# BlueSMiRF-ChipAnt.net
KiCad netlist of a schematic drawn in EAGLE
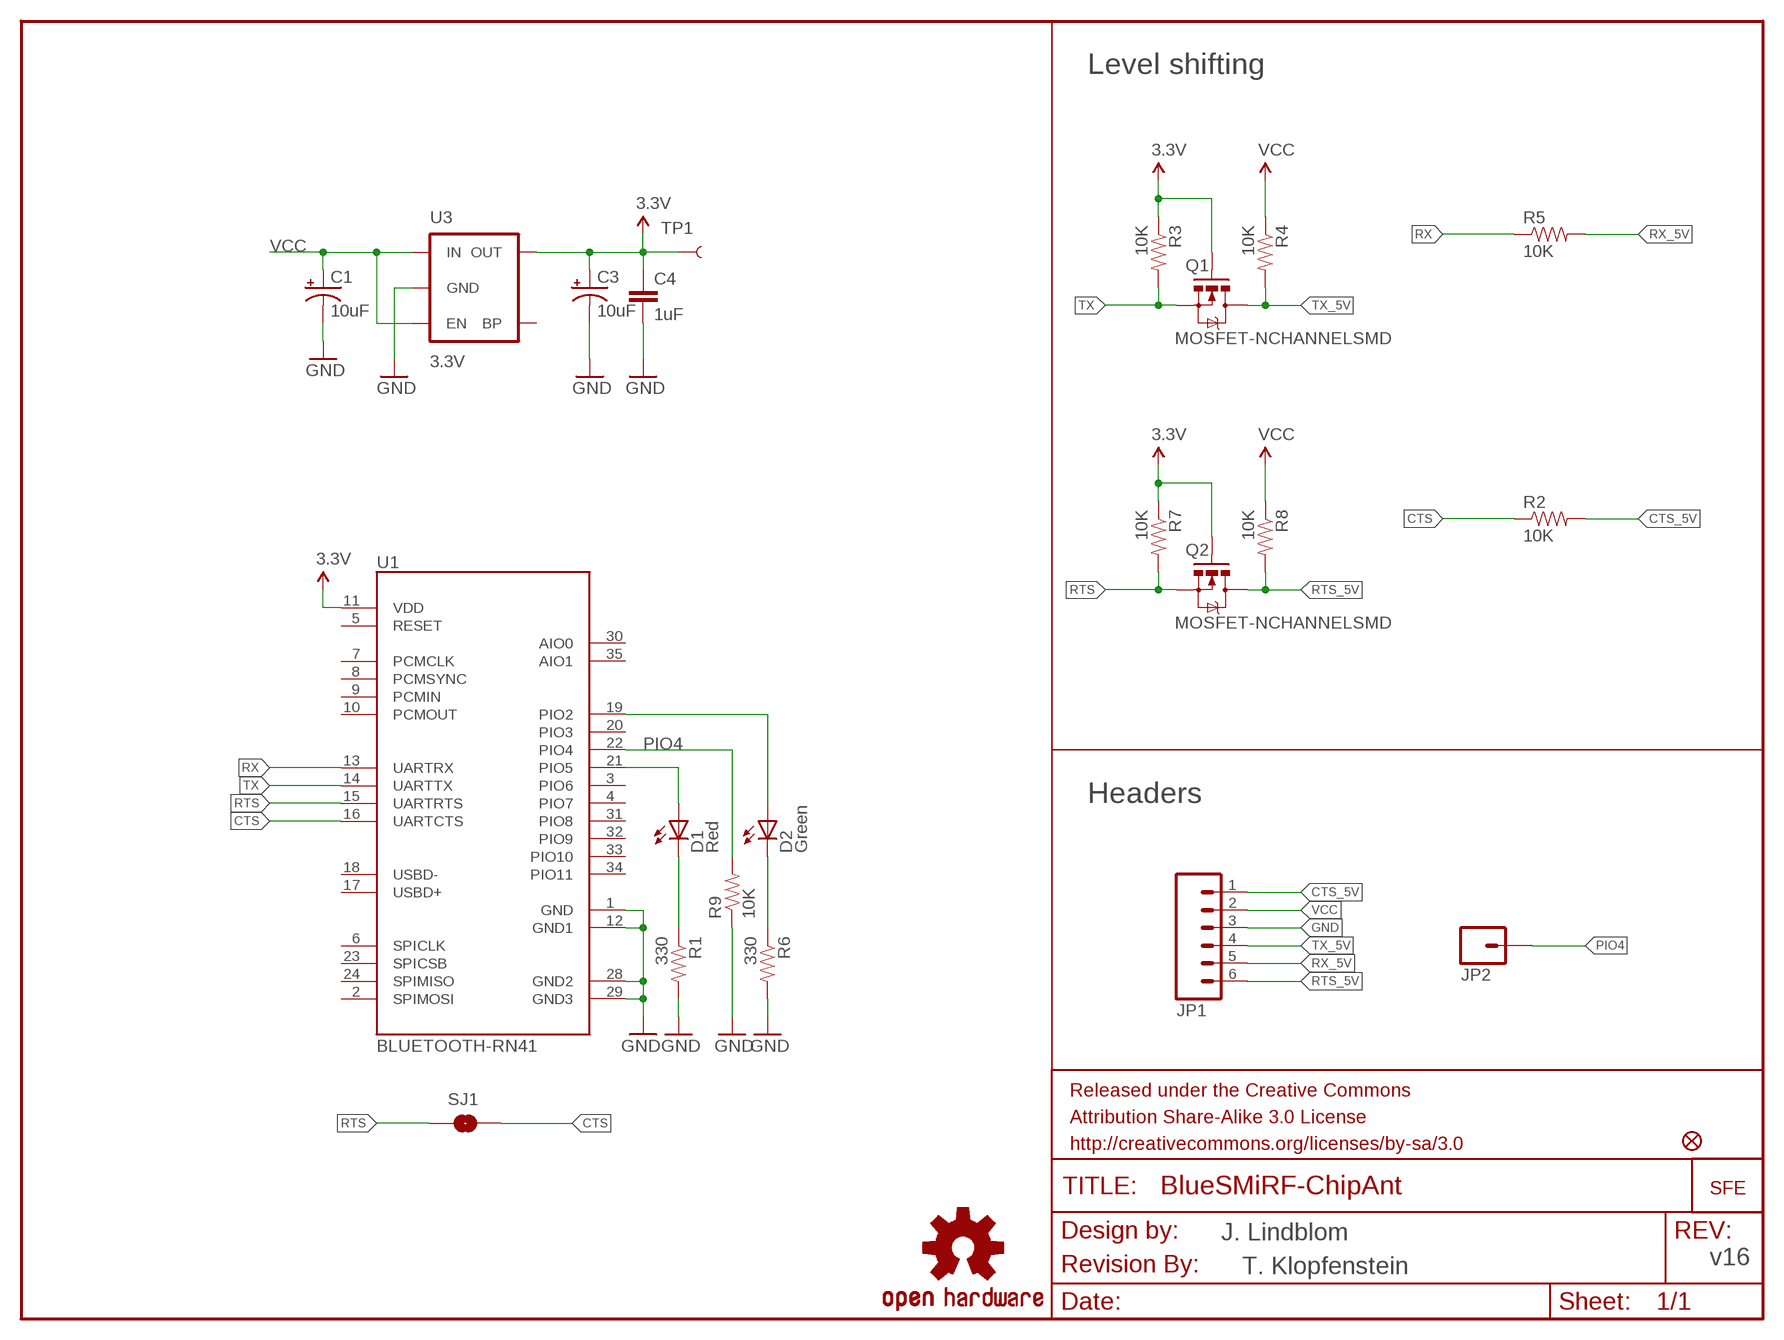
[diagram p0: schematic, sheet 1]

(export (version "E")
  (design (tool "Eeschema 10.0.6"))
  (components
    (comp (ref "C1")
      (value "10uF")
      (footprint "eagle-import:EIA3216")
      (libsource (lib "eagle-import") (part "CAP_POL1206"))
    )
    (comp (ref "C3")
      (value "10uF")
      (footprint "eagle-import:EIA3216")
      (libsource (lib "eagle-import") (part "CAP_POL1206"))
    )
    (comp (ref "C4")
      (value "1uF")
      (footprint "eagle-import:0603-CAP")
      (libsource (lib "eagle-import") (part "CAP0603-CAP"))
    )
    (comp (ref "D1")
      (value "Red")
      (footprint "eagle-import:LED-0603")
      (libsource (lib "eagle-import") (part "LED0603"))
    )
    (comp (ref "D2")
      (value "Green")
      (footprint "eagle-import:LED-0603")
      (libsource (lib "eagle-import") (part "LED0603"))
    )
    (comp (ref "FRAME1")
      (value "FRAME-LETTER")
      (footprint "eagle-import:CREATIVE_COMMONS")
      (libsource (lib "eagle-import") (part "FRAME-LETTER"))
    )
    (comp (ref "JP1")
      (value "M06SIP")
      (footprint "eagle-import:1X06")
      (libsource (lib "eagle-import") (part "M06SIP"))
    )
    (comp (ref "JP2")
      (value "M01SMDNS")
      (footprint "eagle-import:1X01NS")
      (libsource (lib "eagle-import") (part "M01SMDNS"))
    )
    (comp (ref "JP4")
      (value "FIDUCIAL1X2")
      (footprint "eagle-import:FIDUCIAL-1X2")
      (libsource (lib "eagle-import") (part "FIDUCIAL1X2"))
    )
    (comp (ref "LOGO1")
      (value "OSHW-LOGOS")
      (footprint "eagle-import:OSHW-LOGO-S")
      (libsource (lib "eagle-import") (part "OSHW-LOGOS"))
    )
    (comp (ref "Q1")
      (value "MOSFET-NCHANNELSMD")
      (footprint "eagle-import:SOT23-3")
      (libsource (lib "eagle-import") (part "MOSFET-NCHANNELSMD"))
    )
    (comp (ref "Q2")
      (value "MOSFET-NCHANNELSMD")
      (footprint "eagle-import:SOT23-3")
      (libsource (lib "eagle-import") (part "MOSFET-NCHANNELSMD"))
    )
    (comp (ref "R1")
      (value "330")
      (footprint "eagle-import:0603-RES")
      (libsource (lib "eagle-import") (part "RESISTOR0603-RES"))
    )
    (comp (ref "R2")
      (value "10K")
      (footprint "eagle-import:0603-RES")
      (libsource (lib "eagle-import") (part "RESISTOR0603-RES"))
    )
    (comp (ref "R3")
      (value "10K")
      (footprint "eagle-import:0603-RES")
      (libsource (lib "eagle-import") (part "RESISTOR0603-RES"))
    )
    (comp (ref "R4")
      (value "10K")
      (footprint "eagle-import:0603-RES")
      (libsource (lib "eagle-import") (part "RESISTOR0603-RES"))
    )
    (comp (ref "R5")
      (value "10K")
      (footprint "eagle-import:0603-RES")
      (libsource (lib "eagle-import") (part "RESISTOR0603-RES"))
    )
    (comp (ref "R6")
      (value "330")
      (footprint "eagle-import:0603-RES")
      (libsource (lib "eagle-import") (part "RESISTOR0603-RES"))
    )
    (comp (ref "R7")
      (value "10K")
      (footprint "eagle-import:0603-RES")
      (libsource (lib "eagle-import") (part "RESISTOR0603-RES"))
    )
    (comp (ref "R8")
      (value "10K")
      (footprint "eagle-import:0603-RES")
      (libsource (lib "eagle-import") (part "RESISTOR0603-RES"))
    )
    (comp (ref "R9")
      (value "10K")
      (footprint "eagle-import:0603-RES")
      (libsource (lib "eagle-import") (part "RESISTOR0603-RES"))
    )
    (comp (ref "SJ1")
      (value "SOLDERJUMPERNO")
      (footprint "eagle-import:SJ_2S-NO")
      (libsource (lib "eagle-import") (part "SOLDERJUMPERNO"))
    )
    (comp (ref "TP1")
      (value "TEST-POINT3X5")
      (footprint "eagle-import:PAD.03X.05")
      (libsource (lib "eagle-import") (part "TEST-POINT3X5"))
    )
    (comp (ref "U$1")
      (value "LOGO-SFENEW")
      (footprint "eagle-import:SFE-NEW-WEBLOGO")
      (libsource (lib "eagle-import") (part "LOGO-SFENEW"))
    )
    (comp (ref "U$2")
      (value "REVISION")
      (footprint "eagle-import:REVISION")
      (libsource (lib "eagle-import") (part "REVISION"))
    )
    (comp (ref "U1")
      (value "BLUETOOTH-RN41")
      (footprint "eagle-import:RN41")
      (libsource (lib "eagle-import") (part "BLUETOOTH-RN41{dblquote}"))
    )
    (comp (ref "U3")
      (value "3.3V")
      (footprint "eagle-import:SOT23-5")
      (libsource (lib "eagle-import") (part "V_REG_LDOSMD"))
    )
  )
  (nets
    (net (code "1") (name "3.3V") (class "Default")
      (node (ref "C3") (pin "A") (pinfunction "+_A") (pintype "passive"))
      (node (ref "C4") (pin "1") (pinfunction "1_1") (pintype "passive"))
      (node (ref "Q1") (pin "1") (pinfunction "G_1") (pintype "passive"))
      (node (ref "Q2") (pin "1") (pinfunction "G_1") (pintype "passive"))
      (node (ref "R3") (pin "1") (pinfunction "1_1") (pintype "passive"))
      (node (ref "R7") (pin "1") (pinfunction "1_1") (pintype "passive"))
      (node (ref "TP1") (pin "P$1") (pinfunction "1_P$1") (pintype "bidirectional"))
      (node (ref "U1") (pin "11") (pinfunction "VDD_11") (pintype "bidirectional"))
      (node (ref "U3") (pin "5") (pinfunction "OUT_5") (pintype "passive"))
    )
    (net (code "2") (name "CTS") (class "Default")
      (node (ref "R2") (pin "1") (pinfunction "1_1") (pintype "passive"))
      (node (ref "SJ1") (pin "2") (pinfunction "2_2") (pintype "passive"))
      (node (ref "U1") (pin "16") (pinfunction "UARTCTS_16") (pintype "bidirectional"))
    )
    (net (code "3") (name "CTS_5V") (class "Default")
      (node (ref "JP1") (pin "1") (pinfunction "1_1") (pintype "passive"))
      (node (ref "R2") (pin "2") (pinfunction "2_2") (pintype "passive"))
    )
    (net (code "4") (name "GND") (class "Default")
      (node (ref "C1") (pin "C") (pinfunction "-_C") (pintype "passive"))
      (node (ref "C3") (pin "C") (pinfunction "-_C") (pintype "passive"))
      (node (ref "C4") (pin "2") (pinfunction "2_2") (pintype "passive"))
      (node (ref "JP1") (pin "3") (pinfunction "3_3") (pintype "passive"))
      (node (ref "R1") (pin "2") (pinfunction "2_2") (pintype "passive"))
      (node (ref "R6") (pin "2") (pinfunction "2_2") (pintype "passive"))
      (node (ref "R9") (pin "1") (pinfunction "1_1") (pintype "passive"))
      (node (ref "U1") (pin "1") (pinfunction "GND_1") (pintype "bidirectional"))
      (node (ref "U1") (pin "12") (pinfunction "GND1_12") (pintype "bidirectional"))
      (node (ref "U1") (pin "28") (pinfunction "GND2_28") (pintype "bidirectional"))
      (node (ref "U1") (pin "29") (pinfunction "GND3_29") (pintype "bidirectional"))
      (node (ref "U3") (pin "2") (pinfunction "GND_2") (pintype "input"))
    )
    (net (code "5") (name "Net-(D1-PadC)") (class "Default")
      (node (ref "D1") (pin "C") (pinfunction "C_C") (pintype "passive"))
      (node (ref "R1") (pin "1") (pinfunction "1_1") (pintype "passive"))
    )
    (net (code "6") (name "Net-(D2-PadC)") (class "Default")
      (node (ref "D2") (pin "C") (pinfunction "C_C") (pintype "passive"))
      (node (ref "R6") (pin "1") (pinfunction "1_1") (pintype "passive"))
    )
    (net (code "7") (name "Net-(U1-PIO2)") (class "Default")
      (node (ref "D2") (pin "A") (pinfunction "A_A") (pintype "passive"))
      (node (ref "U1") (pin "19") (pinfunction "PIO2_19") (pintype "bidirectional"))
    )
    (net (code "8") (name "Net-(U1-PIO5)") (class "Default")
      (node (ref "D1") (pin "A") (pinfunction "A_A") (pintype "passive"))
      (node (ref "U1") (pin "21") (pinfunction "PIO5_21") (pintype "bidirectional"))
    )
    (net (code "9") (name "PIO4") (class "Default")
      (node (ref "JP2") (pin "1") (pinfunction "1_1") (pintype "passive"))
      (node (ref "R9") (pin "2") (pinfunction "2_2") (pintype "passive"))
      (node (ref "U1") (pin "22") (pinfunction "PIO4_22") (pintype "bidirectional"))
    )
    (net (code "10") (name "RTS") (class "Default")
      (node (ref "Q2") (pin "2") (pinfunction "S_2") (pintype "passive"))
      (node (ref "R7") (pin "2") (pinfunction "2_2") (pintype "passive"))
      (node (ref "SJ1") (pin "1") (pinfunction "1_1") (pintype "passive"))
      (node (ref "U1") (pin "15") (pinfunction "UARTRTS_15") (pintype "bidirectional"))
    )
    (net (code "11") (name "RTS_5V") (class "Default")
      (node (ref "JP1") (pin "6") (pinfunction "6_6") (pintype "passive"))
      (node (ref "Q2") (pin "3") (pinfunction "D_3") (pintype "passive"))
      (node (ref "R8") (pin "2") (pinfunction "2_2") (pintype "passive"))
    )
    (net (code "12") (name "RX") (class "Default")
      (node (ref "R5") (pin "1") (pinfunction "1_1") (pintype "passive"))
      (node (ref "U1") (pin "13") (pinfunction "UARTRX_13") (pintype "bidirectional"))
    )
    (net (code "13") (name "RX_5V") (class "Default")
      (node (ref "JP1") (pin "5") (pinfunction "5_5") (pintype "passive"))
      (node (ref "R5") (pin "2") (pinfunction "2_2") (pintype "passive"))
    )
    (net (code "14") (name "TX") (class "Default")
      (node (ref "Q1") (pin "2") (pinfunction "S_2") (pintype "passive"))
      (node (ref "R3") (pin "2") (pinfunction "2_2") (pintype "passive"))
      (node (ref "U1") (pin "14") (pinfunction "UARTTX_14") (pintype "bidirectional"))
    )
    (net (code "15") (name "TX_5V") (class "Default")
      (node (ref "JP1") (pin "4") (pinfunction "4_4") (pintype "passive"))
      (node (ref "Q1") (pin "3") (pinfunction "D_3") (pintype "passive"))
      (node (ref "R4") (pin "2") (pinfunction "2_2") (pintype "passive"))
    )
    (net (code "16") (name "VCC") (class "Default")
      (node (ref "C1") (pin "A") (pinfunction "+_A") (pintype "passive"))
      (node (ref "JP1") (pin "2") (pinfunction "2_2") (pintype "passive"))
      (node (ref "R4") (pin "1") (pinfunction "1_1") (pintype "passive"))
      (node (ref "R8") (pin "1") (pinfunction "1_1") (pintype "passive"))
      (node (ref "U3") (pin "1") (pinfunction "IN_1") (pintype "input"))
      (node (ref "U3") (pin "3") (pinfunction "EN_3") (pintype "input"))
    )
    (net (code "17") (name "unconnected-(U1-AIO0-Pad30)") (class "Default")
      (node (ref "U1") (pin "30") (pinfunction "AIO0_30") (pintype "bidirectional"))
    )
    (net (code "18") (name "unconnected-(U1-AIO1-Pad35)") (class "Default")
      (node (ref "U1") (pin "35") (pinfunction "AIO1_35") (pintype "bidirectional"))
    )
    (net (code "19") (name "unconnected-(U1-PCMCLK-Pad7)") (class "Default")
      (node (ref "U1") (pin "7") (pinfunction "PCMCLK_7") (pintype "bidirectional"))
    )
    (net (code "20") (name "unconnected-(U1-PCMIN-Pad9)") (class "Default")
      (node (ref "U1") (pin "9") (pinfunction "PCMIN_9") (pintype "bidirectional"))
    )
    (net (code "21") (name "unconnected-(U1-PCMOUT-Pad10)") (class "Default")
      (node (ref "U1") (pin "10") (pinfunction "PCMOUT_10") (pintype "bidirectional"))
    )
    (net (code "22") (name "unconnected-(U1-PCMSYNC-Pad8)") (class "Default")
      (node (ref "U1") (pin "8") (pinfunction "PCMSYNC_8") (pintype "bidirectional"))
    )
    (net (code "23") (name "unconnected-(U1-PIO3-Pad20)") (class "Default")
      (node (ref "U1") (pin "20") (pinfunction "PIO3_20") (pintype "bidirectional"))
    )
    (net (code "24") (name "unconnected-(U1-PIO6-Pad3)") (class "Default")
      (node (ref "U1") (pin "3") (pinfunction "PIO6_3") (pintype "bidirectional"))
    )
    (net (code "25") (name "unconnected-(U1-PIO7-Pad4)") (class "Default")
      (node (ref "U1") (pin "4") (pinfunction "PIO7_4") (pintype "bidirectional"))
    )
    (net (code "26") (name "unconnected-(U1-PIO8-Pad31)") (class "Default")
      (node (ref "U1") (pin "31") (pinfunction "PIO8_31") (pintype "bidirectional"))
    )
    (net (code "27") (name "unconnected-(U1-PIO9-Pad32)") (class "Default")
      (node (ref "U1") (pin "32") (pinfunction "PIO9_32") (pintype "bidirectional"))
    )
    (net (code "28") (name "unconnected-(U1-PIO10-Pad33)") (class "Default")
      (node (ref "U1") (pin "33") (pinfunction "PIO10_33") (pintype "bidirectional"))
    )
    (net (code "29") (name "unconnected-(U1-PIO11-Pad34)") (class "Default")
      (node (ref "U1") (pin "34") (pinfunction "PIO11_34") (pintype "bidirectional"))
    )
    (net (code "30") (name "unconnected-(U1-RESET-Pad5)") (class "Default")
      (node (ref "U1") (pin "5") (pinfunction "RESET_5") (pintype "bidirectional"))
    )
    (net (code "31") (name "unconnected-(U1-SPICLK-Pad6)") (class "Default")
      (node (ref "U1") (pin "6") (pinfunction "SPICLK_6") (pintype "bidirectional"))
    )
    (net (code "32") (name "unconnected-(U1-SPICSB-Pad23)") (class "Default")
      (node (ref "U1") (pin "23") (pinfunction "SPICSB_23") (pintype "bidirectional"))
    )
    (net (code "33") (name "unconnected-(U1-SPIMISO-Pad24)") (class "Default")
      (node (ref "U1") (pin "24") (pinfunction "SPIMISO_24") (pintype "bidirectional"))
    )
    (net (code "34") (name "unconnected-(U1-SPIMOSI-Pad2)") (class "Default")
      (node (ref "U1") (pin "2") (pinfunction "SPIMOSI_2") (pintype "bidirectional"))
    )
    (net (code "35") (name "unconnected-(U1-USBD+-Pad17)") (class "Default")
      (node (ref "U1") (pin "17") (pinfunction "USBD+_17") (pintype "bidirectional"))
    )
    (net (code "36") (name "unconnected-(U1-USBD--Pad18)") (class "Default")
      (node (ref "U1") (pin "18") (pinfunction "USBD-_18") (pintype "bidirectional"))
    )
    (net (code "37") (name "unconnected-(U3-BP-Pad4)") (class "Default")
      (node (ref "U3") (pin "4") (pinfunction "BP_4") (pintype "input"))
    )
  )
)
